# controller.net
KiCad netlist of a schematic drawn in EAGLE
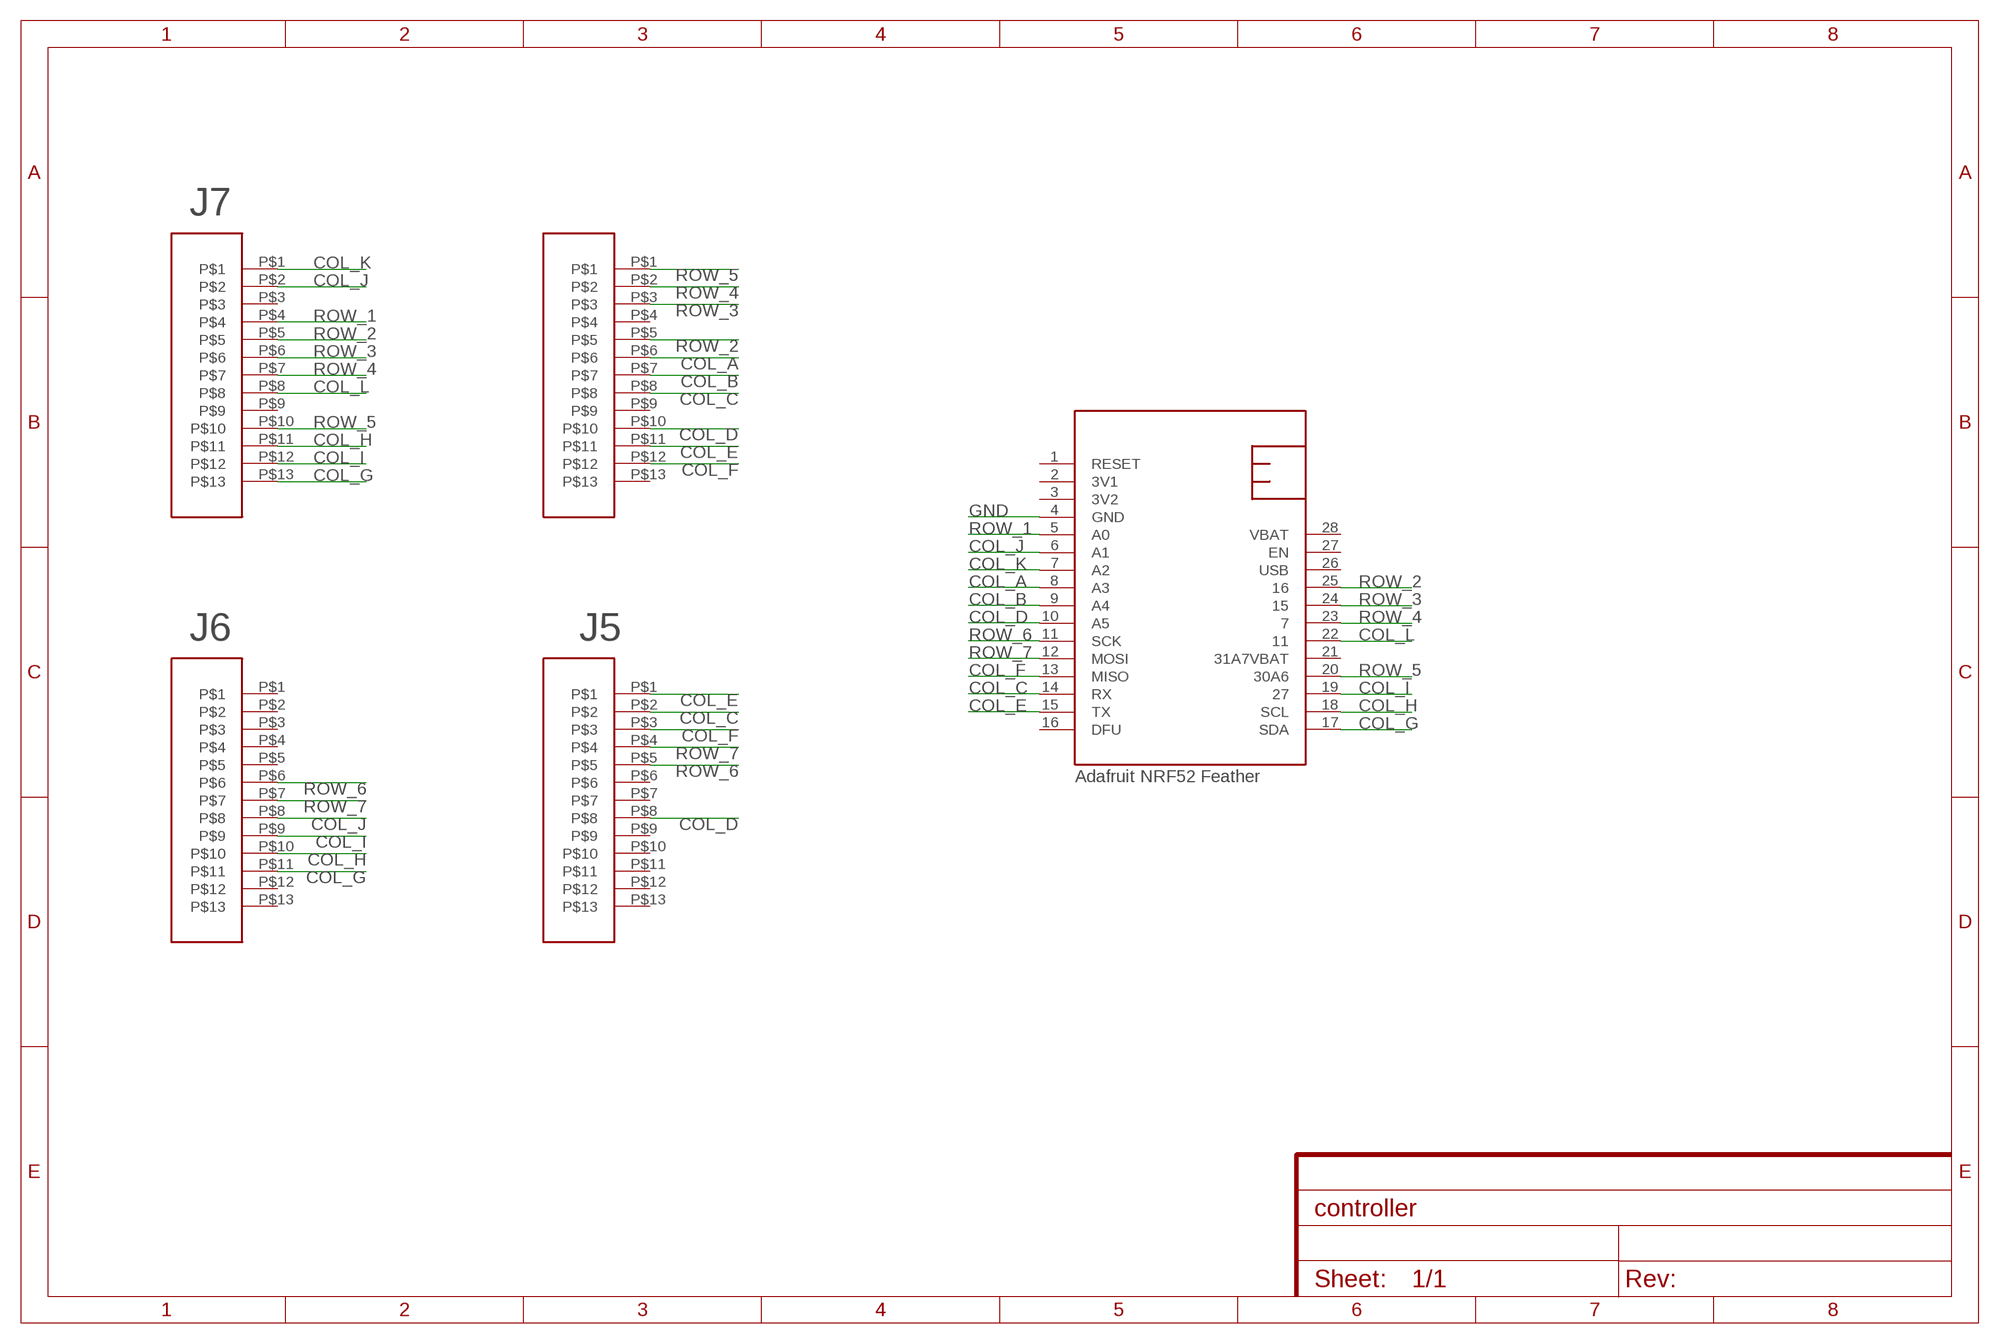
[diagram p0: schematic, sheet 1]

(export (version "E")
  (design (tool "Eeschema 10.0.6"))
  (components
    (comp (ref "U$1")
      (value "NRF52FEATHER")
      (footprint "eagle-import:NRF52FEATHER")
      (libsource (lib "eagle-import") (part "NRF52FEATHER"))
    )
    (comp (ref "U$4")
      (value "TOPLINKS_STAPELBERG")
      (footprint "eagle-import:TOPLINKS_STAPELBERG")
      (libsource (lib "eagle-import") (part "TOPLINKS_STAPELBERG"))
    )
    (comp (ref "U$5")
      (value "TOPLINKS_STAPELBERG")
      (footprint "eagle-import:TOPLINKS_STAPELBERG")
      (libsource (lib "eagle-import") (part "TOPLINKS_STAPELBERG"))
    )
    (comp (ref "U$6")
      (value "TOPLINKS_STAPELBERG")
      (footprint "eagle-import:TOPLINKS_STAPELBERG")
      (libsource (lib "eagle-import") (part "TOPLINKS_STAPELBERG"))
    )
    (comp (ref "U$7")
      (value "TOPLINKS_STAPELBERG")
      (footprint "eagle-import:TOPLINKS_STAPELBERG")
      (libsource (lib "eagle-import") (part "TOPLINKS_STAPELBERG"))
    )
  )
  (nets
    (net (code "1") (name "/3V1") (class "Default")
      (node (ref "U$1") (pin "2") (pinfunction "3V1_2") (pintype "power_in"))
    )
    (net (code "2") (name "/3V2") (class "Default")
      (node (ref "U$1") (pin "3") (pinfunction "3V2_3") (pintype "power_in"))
    )
    (net (code "3") (name "/COL_A") (class "Default")
      (node (ref "U$1") (pin "8") (pinfunction "A3_8") (pintype "bidirectional"))
      (node (ref "U$5") (pin "P$6") (pinfunction "P$6_P$6") (pintype "bidirectional"))
    )
    (net (code "4") (name "/COL_B") (class "Default")
      (node (ref "U$1") (pin "9") (pinfunction "A4_9") (pintype "bidirectional"))
      (node (ref "U$5") (pin "P$7") (pinfunction "P$7_P$7") (pintype "bidirectional"))
    )
    (net (code "5") (name "/COL_C") (class "Default")
      (node (ref "U$1") (pin "14") (pinfunction "RX_14") (pintype "bidirectional"))
      (node (ref "U$5") (pin "P$8") (pinfunction "P$8_P$8") (pintype "bidirectional"))
      (node (ref "U$6") (pin "P$2") (pinfunction "P$2_P$2") (pintype "bidirectional"))
    )
    (net (code "6") (name "/COL_D") (class "Default")
      (node (ref "U$1") (pin "10") (pinfunction "A5_10") (pintype "bidirectional"))
      (node (ref "U$5") (pin "P$10") (pinfunction "P$10_P$10") (pintype "bidirectional"))
      (node (ref "U$6") (pin "P$8") (pinfunction "P$8_P$8") (pintype "bidirectional"))
    )
    (net (code "7") (name "/COL_E") (class "Default")
      (node (ref "U$1") (pin "15") (pinfunction "TX_15") (pintype "bidirectional"))
      (node (ref "U$5") (pin "P$11") (pinfunction "P$11_P$11") (pintype "bidirectional"))
      (node (ref "U$6") (pin "P$1") (pinfunction "P$1_P$1") (pintype "bidirectional"))
    )
    (net (code "8") (name "/COL_F") (class "Default")
      (node (ref "U$1") (pin "13") (pinfunction "MISO_13") (pintype "bidirectional"))
      (node (ref "U$5") (pin "P$12") (pinfunction "P$12_P$12") (pintype "bidirectional"))
      (node (ref "U$6") (pin "P$3") (pinfunction "P$3_P$3") (pintype "bidirectional"))
    )
    (net (code "9") (name "/COL_G") (class "Default")
      (node (ref "U$1") (pin "17") (pinfunction "SDA_17") (pintype "bidirectional"))
      (node (ref "U$4") (pin "P$13") (pinfunction "P$13_P$13") (pintype "bidirectional"))
      (node (ref "U$7") (pin "P$11") (pinfunction "P$11_P$11") (pintype "bidirectional"))
    )
    (net (code "10") (name "/COL_H") (class "Default")
      (node (ref "U$1") (pin "18") (pinfunction "SCL_18") (pintype "bidirectional"))
      (node (ref "U$4") (pin "P$11") (pinfunction "P$11_P$11") (pintype "bidirectional"))
      (node (ref "U$7") (pin "P$10") (pinfunction "P$10_P$10") (pintype "bidirectional"))
    )
    (net (code "11") (name "/COL_I") (class "Default")
      (node (ref "U$1") (pin "19") (pinfunction "27_19") (pintype "bidirectional"))
      (node (ref "U$4") (pin "P$12") (pinfunction "P$12_P$12") (pintype "bidirectional"))
      (node (ref "U$7") (pin "P$9") (pinfunction "P$9_P$9") (pintype "bidirectional"))
    )
    (net (code "12") (name "/COL_J") (class "Default")
      (node (ref "U$1") (pin "6") (pinfunction "A1_6") (pintype "bidirectional"))
      (node (ref "U$4") (pin "P$2") (pinfunction "P$2_P$2") (pintype "bidirectional"))
      (node (ref "U$7") (pin "P$8") (pinfunction "P$8_P$8") (pintype "bidirectional"))
    )
    (net (code "13") (name "/COL_K") (class "Default")
      (node (ref "U$1") (pin "7") (pinfunction "A2_7") (pintype "bidirectional"))
      (node (ref "U$4") (pin "P$1") (pinfunction "P$1_P$1") (pintype "bidirectional"))
    )
    (net (code "14") (name "/COL_L") (class "Default")
      (node (ref "U$1") (pin "22") (pinfunction "11_22") (pintype "bidirectional"))
      (node (ref "U$4") (pin "P$8") (pinfunction "P$8_P$8") (pintype "bidirectional"))
    )
    (net (code "15") (name "/GND") (class "Default")
      (node (ref "U$1") (pin "4") (pinfunction "GND_4") (pintype "bidirectional"))
    )
    (net (code "16") (name "/ROW_1") (class "Default")
      (node (ref "U$1") (pin "5") (pinfunction "A0_5") (pintype "bidirectional"))
      (node (ref "U$4") (pin "P$4") (pinfunction "P$4_P$4") (pintype "bidirectional"))
    )
    (net (code "17") (name "/ROW_2") (class "Default")
      (node (ref "U$1") (pin "25") (pinfunction "16_25") (pintype "bidirectional"))
      (node (ref "U$4") (pin "P$5") (pinfunction "P$5_P$5") (pintype "bidirectional"))
      (node (ref "U$5") (pin "P$5") (pinfunction "P$5_P$5") (pintype "bidirectional"))
    )
    (net (code "18") (name "/ROW_3") (class "Default")
      (node (ref "U$1") (pin "24") (pinfunction "15_24") (pintype "bidirectional"))
      (node (ref "U$4") (pin "P$6") (pinfunction "P$6_P$6") (pintype "bidirectional"))
      (node (ref "U$5") (pin "P$3") (pinfunction "P$3_P$3") (pintype "bidirectional"))
    )
    (net (code "19") (name "/ROW_4") (class "Default")
      (node (ref "U$1") (pin "23") (pinfunction "7_23") (pintype "bidirectional"))
      (node (ref "U$4") (pin "P$7") (pinfunction "P$7_P$7") (pintype "bidirectional"))
      (node (ref "U$5") (pin "P$2") (pinfunction "P$2_P$2") (pintype "bidirectional"))
    )
    (net (code "20") (name "/ROW_5") (class "Default")
      (node (ref "U$1") (pin "20") (pinfunction "30A6_20") (pintype "bidirectional"))
      (node (ref "U$4") (pin "P$10") (pinfunction "P$10_P$10") (pintype "bidirectional"))
      (node (ref "U$5") (pin "P$1") (pinfunction "P$1_P$1") (pintype "bidirectional"))
    )
    (net (code "21") (name "/ROW_6") (class "Default")
      (node (ref "U$1") (pin "11") (pinfunction "SCK_11") (pintype "bidirectional"))
      (node (ref "U$6") (pin "P$5") (pinfunction "P$5_P$5") (pintype "bidirectional"))
      (node (ref "U$7") (pin "P$6") (pinfunction "P$6_P$6") (pintype "bidirectional"))
    )
    (net (code "22") (name "/ROW_7") (class "Default")
      (node (ref "U$1") (pin "12") (pinfunction "MOSI_12") (pintype "bidirectional"))
      (node (ref "U$6") (pin "P$4") (pinfunction "P$4_P$4") (pintype "bidirectional"))
      (node (ref "U$7") (pin "P$7") (pinfunction "P$7_P$7") (pintype "bidirectional"))
    )
    (net (code "23") (name "/VBAT") (class "Default")
      (node (ref "U$1") (pin "28") (pinfunction "VBAT_28") (pintype "power_in"))
    )
    (net (code "24") (name "unconnected-(U$1-31A7VBAT-Pad21)") (class "Default")
      (node (ref "U$1") (pin "21") (pinfunction "31A7VBAT_21") (pintype "bidirectional"))
    )
    (net (code "25") (name "unconnected-(U$1-DFU-Pad16)") (class "Default")
      (node (ref "U$1") (pin "16") (pinfunction "DFU_16") (pintype "no_connect"))
    )
    (net (code "26") (name "unconnected-(U$1-EN-Pad27)") (class "Default")
      (node (ref "U$1") (pin "27") (pinfunction "EN_27") (pintype "no_connect"))
    )
    (net (code "27") (name "unconnected-(U$1-RESET-Pad1)") (class "Default")
      (node (ref "U$1") (pin "1") (pinfunction "RESET_1") (pintype "no_connect"))
    )
    (net (code "28") (name "unconnected-(U$1-USB-Pad26)") (class "Default")
      (node (ref "U$1") (pin "26") (pinfunction "USB_26") (pintype "bidirectional"))
    )
    (net (code "29") (name "unconnected-(U$4-PadP$3)") (class "Default")
      (node (ref "U$4") (pin "P$3") (pinfunction "P$3_P$3") (pintype "bidirectional"))
    )
    (net (code "30") (name "unconnected-(U$4-PadP$9)") (class "Default")
      (node (ref "U$4") (pin "P$9") (pinfunction "P$9_P$9") (pintype "bidirectional"))
    )
    (net (code "31") (name "unconnected-(U$5-PadP$4)") (class "Default")
      (node (ref "U$5") (pin "P$4") (pinfunction "P$4_P$4") (pintype "bidirectional"))
    )
    (net (code "32") (name "unconnected-(U$5-PadP$9)") (class "Default")
      (node (ref "U$5") (pin "P$9") (pinfunction "P$9_P$9") (pintype "bidirectional"))
    )
    (net (code "33") (name "unconnected-(U$5-PadP$13)") (class "Default")
      (node (ref "U$5") (pin "P$13") (pinfunction "P$13_P$13") (pintype "bidirectional"))
    )
    (net (code "34") (name "unconnected-(U$6-PadP$6)") (class "Default")
      (node (ref "U$6") (pin "P$6") (pinfunction "P$6_P$6") (pintype "bidirectional"))
    )
    (net (code "35") (name "unconnected-(U$6-PadP$7)") (class "Default")
      (node (ref "U$6") (pin "P$7") (pinfunction "P$7_P$7") (pintype "bidirectional"))
    )
    (net (code "36") (name "unconnected-(U$6-PadP$9)") (class "Default")
      (node (ref "U$6") (pin "P$9") (pinfunction "P$9_P$9") (pintype "bidirectional"))
    )
    (net (code "37") (name "unconnected-(U$6-PadP$10)") (class "Default")
      (node (ref "U$6") (pin "P$10") (pinfunction "P$10_P$10") (pintype "bidirectional"))
    )
    (net (code "38") (name "unconnected-(U$6-PadP$11)") (class "Default")
      (node (ref "U$6") (pin "P$11") (pinfunction "P$11_P$11") (pintype "bidirectional"))
    )
    (net (code "39") (name "unconnected-(U$6-PadP$12)") (class "Default")
      (node (ref "U$6") (pin "P$12") (pinfunction "P$12_P$12") (pintype "bidirectional"))
    )
    (net (code "40") (name "unconnected-(U$6-PadP$13)") (class "Default")
      (node (ref "U$6") (pin "P$13") (pinfunction "P$13_P$13") (pintype "bidirectional"))
    )
    (net (code "41") (name "unconnected-(U$7-PadP$1)") (class "Default")
      (node (ref "U$7") (pin "P$1") (pinfunction "P$1_P$1") (pintype "bidirectional"))
    )
    (net (code "42") (name "unconnected-(U$7-PadP$2)") (class "Default")
      (node (ref "U$7") (pin "P$2") (pinfunction "P$2_P$2") (pintype "bidirectional"))
    )
    (net (code "43") (name "unconnected-(U$7-PadP$3)") (class "Default")
      (node (ref "U$7") (pin "P$3") (pinfunction "P$3_P$3") (pintype "bidirectional"))
    )
    (net (code "44") (name "unconnected-(U$7-PadP$4)") (class "Default")
      (node (ref "U$7") (pin "P$4") (pinfunction "P$4_P$4") (pintype "bidirectional"))
    )
    (net (code "45") (name "unconnected-(U$7-PadP$5)") (class "Default")
      (node (ref "U$7") (pin "P$5") (pinfunction "P$5_P$5") (pintype "bidirectional"))
    )
    (net (code "46") (name "unconnected-(U$7-PadP$12)") (class "Default")
      (node (ref "U$7") (pin "P$12") (pinfunction "P$12_P$12") (pintype "bidirectional"))
    )
    (net (code "47") (name "unconnected-(U$7-PadP$13)") (class "Default")
      (node (ref "U$7") (pin "P$13") (pinfunction "P$13_P$13") (pintype "bidirectional"))
    )
  )
)
